# tick-mk-3.net
KiCad netlist of a schematic drawn in EAGLE
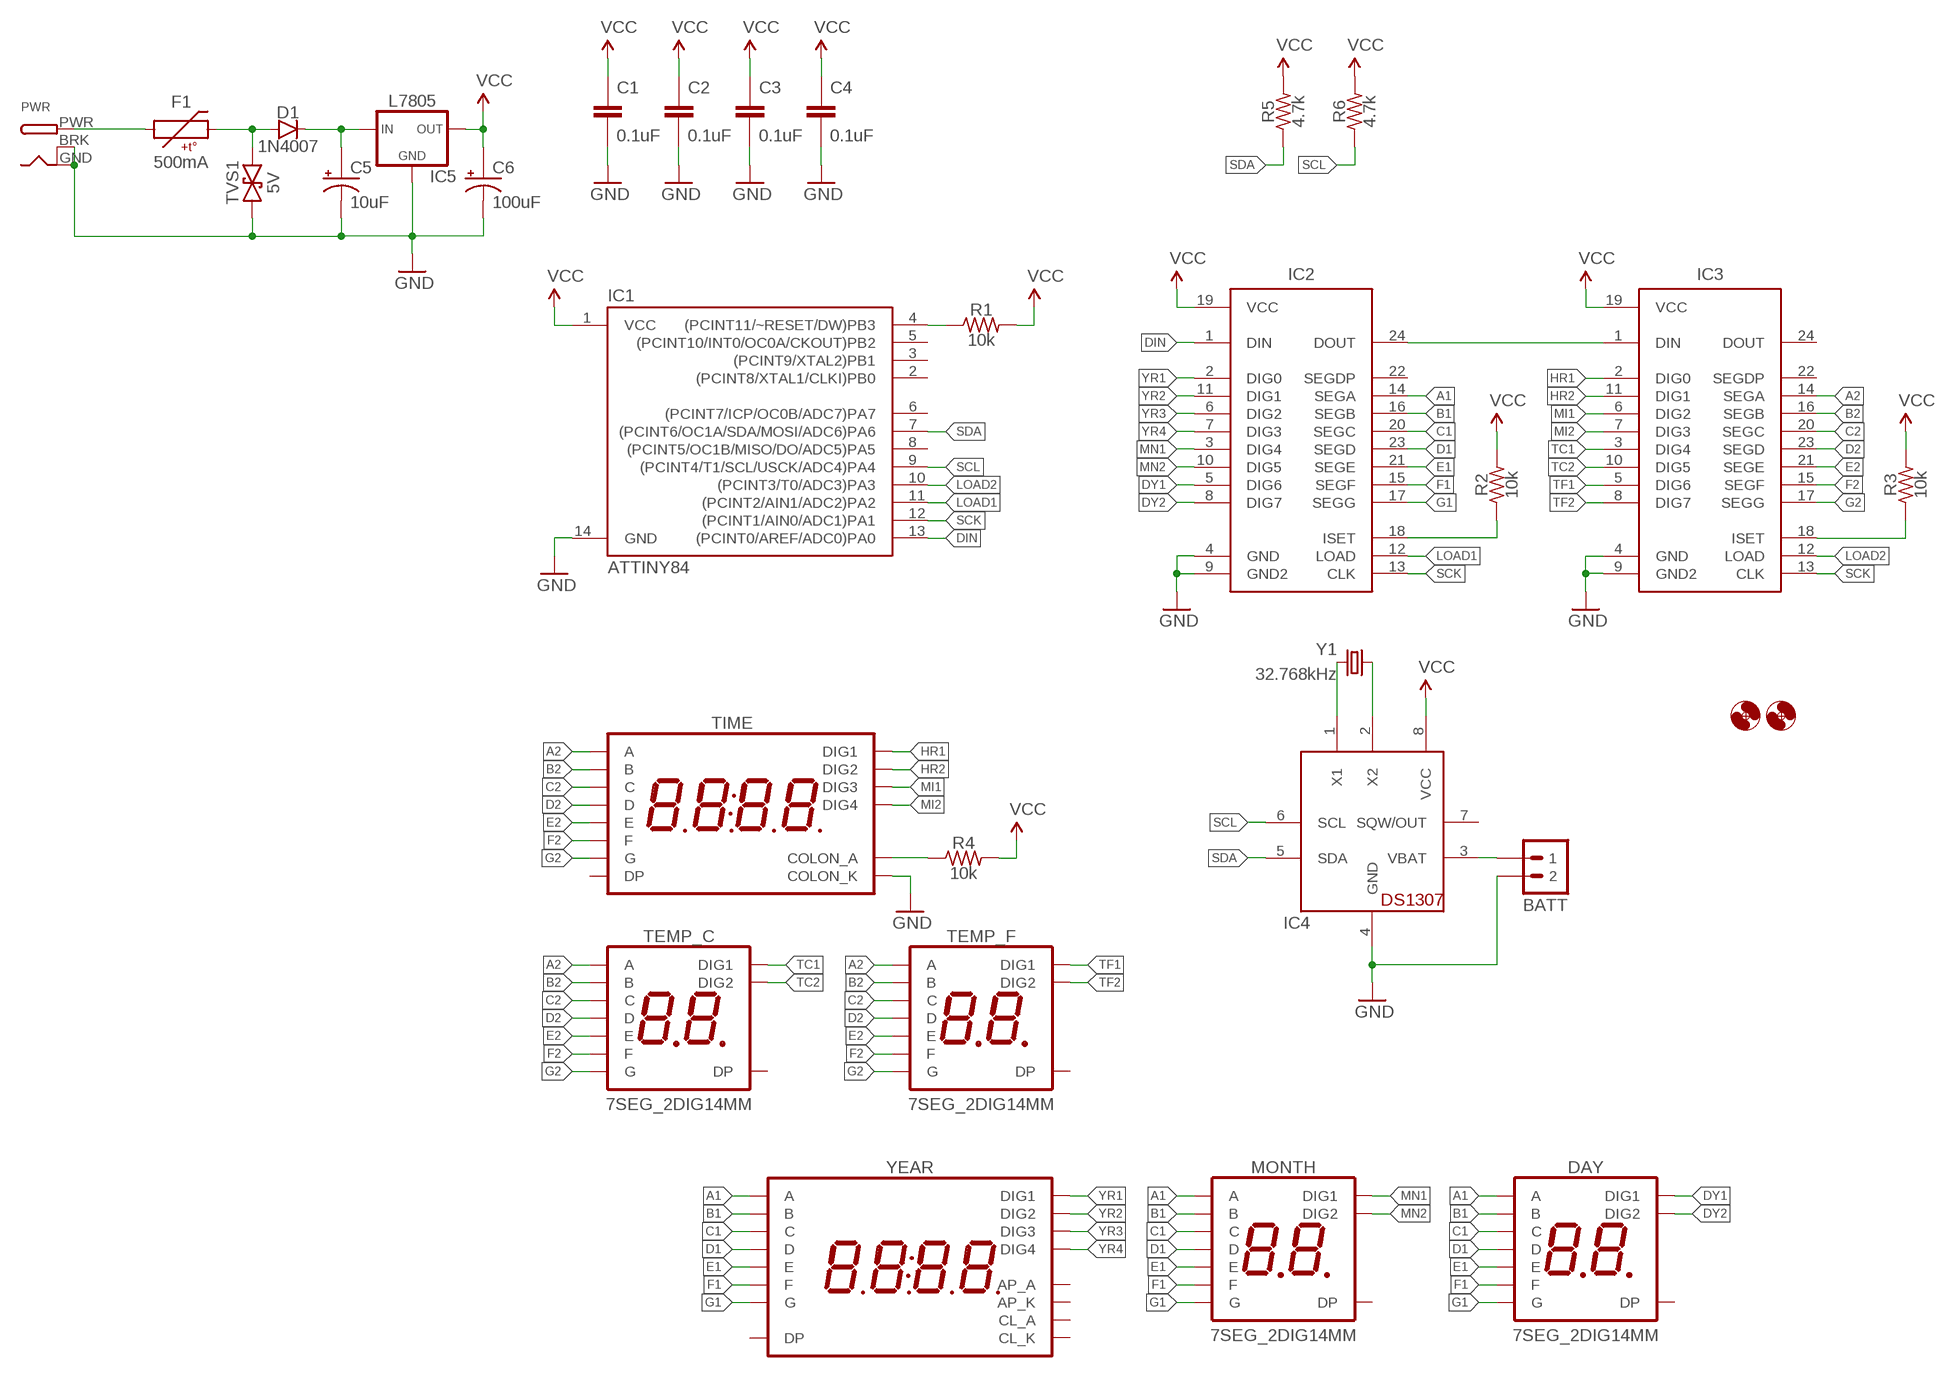
[diagram p0: schematic, sheet 1]

(export (version "E")
  (design (tool "Eeschema 10.0.6"))
  (components
    (comp (ref "BATT")
      (value "M02JST-PTH-VERT")
      (footprint "eagle-import:JST-2-PH-VERT-PTH")
      (libsource (lib "eagle-import") (part "M02JST-PTH-VERT"))
    )
    (comp (ref "C1")
      (value "0.1uF")
      (footprint "eagle-import:C025-024X044")
      (libsource (lib "eagle-import") (part "CAPACITOR-CERAMIC025-024X044"))
    )
    (comp (ref "C2")
      (value "0.1uF")
      (footprint "eagle-import:C025-024X044")
      (libsource (lib "eagle-import") (part "CAPACITOR-CERAMIC025-024X044"))
    )
    (comp (ref "C3")
      (value "0.1uF")
      (footprint "eagle-import:C025-024X044")
      (libsource (lib "eagle-import") (part "CAPACITOR-CERAMIC025-024X044"))
    )
    (comp (ref "C4")
      (value "0.1uF")
      (footprint "eagle-import:C025-024X044")
      (libsource (lib "eagle-import") (part "CAPACITOR-CERAMIC025-024X044"))
    )
    (comp (ref "C5")
      (value "10uF")
      (footprint "eagle-import:E2-5")
      (libsource (lib "eagle-import") (part "CAPACITOR-POLARIZEDE2-5"))
    )
    (comp (ref "C6")
      (value "100uF")
      (footprint "eagle-import:E2-5")
      (libsource (lib "eagle-import") (part "CAPACITOR-POLARIZEDE2-5"))
    )
    (comp (ref "D1")
      (value "1N4007")
      (footprint "eagle-import:DIODE-10.16MM")
      (libsource (lib "eagle-import") (part "DIODEPTH-10.68MM"))
    )
    (comp (ref "DAY")
      (value "7SEG_2DIG14MM")
      (footprint "eagle-import:7SEG_2DIG_14MM")
      (libsource (lib "eagle-import") (part "7SEG_2DIG14MM"))
    )
    (comp (ref "F1")
      (value "500mA")
      (footprint "eagle-import:PTC-PTH-5.08MM")
      (libsource (lib "eagle-import") (part "PTCPTH-5.08MM"))
    )
    (comp (ref "H1")
      (value "HOLE#2")
      (footprint "eagle-import:HOLE-#2")
      (libsource (lib "eagle-import") (part "HOLE#2"))
    )
    (comp (ref "H2")
      (value "HOLE#2")
      (footprint "eagle-import:HOLE-#2")
      (libsource (lib "eagle-import") (part "HOLE#2"))
    )
    (comp (ref "IC1")
      (value "ATTINY84")
      (footprint "eagle-import:SO14")
      (libsource (lib "eagle-import") (part "ATTINY84"))
    )
    (comp (ref "IC2")
      (value "MAX7219")
      (footprint "eagle-import:SO24W")
      (libsource (lib "eagle-import") (part "MAX7219SOIC-W"))
    )
    (comp (ref "IC3")
      (value "MAX7219")
      (footprint "eagle-import:SO24W")
      (libsource (lib "eagle-import") (part "MAX7219SOIC-W"))
    )
    (comp (ref "IC4")
      (value "DS1307")
      (footprint "eagle-import:DIL08")
      (libsource (lib "eagle-import") (part "DS1307"))
    )
    (comp (ref "IC5")
      (value "L7805")
      (footprint "eagle-import:78XXL")
      (libsource (lib "eagle-import") (part "V_REG_78XXSIDE"))
    )
    (comp (ref "MONTH")
      (value "7SEG_2DIG14MM")
      (footprint "eagle-import:7SEG_2DIG_14MM")
      (libsource (lib "eagle-import") (part "7SEG_2DIG14MM"))
    )
    (comp (ref "PWR")
      (value "DCBARRELPTH")
      (footprint "eagle-import:DCJACK_2MM_PTH")
      (libsource (lib "eagle-import") (part "DCBARRELPTH"))
    )
    (comp (ref "R1")
      (value "10k")
      (footprint "eagle-import:RESISTOR-AXIAL-PTH-5.08MM")
      (libsource (lib "eagle-import") (part "RESISTORPTH-AXIAL-5.08MM"))
    )
    (comp (ref "R2")
      (value "10k")
      (footprint "eagle-import:RESISTOR-AXIAL-PTH-5.08MM")
      (libsource (lib "eagle-import") (part "RESISTORPTH-AXIAL-5.08MM"))
    )
    (comp (ref "R3")
      (value "10k")
      (footprint "eagle-import:RESISTOR-AXIAL-PTH-5.08MM")
      (libsource (lib "eagle-import") (part "RESISTORPTH-AXIAL-5.08MM"))
    )
    (comp (ref "R4")
      (value "10k")
      (footprint "eagle-import:RESISTOR-AXIAL-PTH-5.08MM")
      (libsource (lib "eagle-import") (part "RESISTORPTH-AXIAL-5.08MM"))
    )
    (comp (ref "R5")
      (value "4.7k")
      (footprint "eagle-import:RESISTOR-AXIAL-PTH-5.08MM")
      (libsource (lib "eagle-import") (part "RESISTORPTH-AXIAL-5.08MM"))
    )
    (comp (ref "R6")
      (value "4.7k")
      (footprint "eagle-import:RESISTOR-AXIAL-PTH-5.08MM")
      (libsource (lib "eagle-import") (part "RESISTORPTH-AXIAL-5.08MM"))
    )
    (comp (ref "TEMP_C")
      (value "7SEG_2DIG14MM")
      (footprint "eagle-import:7SEG_2DIG_14MM")
      (libsource (lib "eagle-import") (part "7SEG_2DIG14MM"))
    )
    (comp (ref "TEMP_F")
      (value "7SEG_2DIG14MM")
      (footprint "eagle-import:7SEG_2DIG_14MM")
      (libsource (lib "eagle-import") (part "7SEG_2DIG14MM"))
    )
    (comp (ref "TIME")
      (value "7SED_4DIGIT_14MM14.2MM-CC")
      (footprint "eagle-import:7SEG_4DIG")
      (libsource (lib "eagle-import") (part "7SED_4DIGIT_14MM14.2MM-CC"))
    )
    (comp (ref "TVS1")
      (value "5V")
      (footprint "eagle-import:DO-41-TVS")
      (libsource (lib "eagle-import") (part "TVSDO-41-TVS-BIDIRECTIONAL"))
    )
    (comp (ref "Y1")
      (value "32.768kHz")
      (footprint "eagle-import:TC26H")
      (libsource (lib "eagle-import") (part "CRYSTALTC26H"))
    )
    (comp (ref "YEAR")
      (value "7SEG_4DIGIT_10MM")
      (footprint "eagle-import:7SEG_4DIG_10MM")
      (libsource (lib "eagle-import") (part "7SEG_4DIGIT_10MM"))
    )
  )
  (nets
    (net (code "1") (name "A1") (class "Default")
      (node (ref "DAY") (pin "4") (pinfunction "A_4") (pintype "passive"))
      (node (ref "IC2") (pin "14") (pinfunction "SEGA_14") (pintype "bidirectional"))
      (node (ref "MONTH") (pin "4") (pinfunction "A_4") (pintype "passive"))
      (node (ref "YEAR") (pin "14") (pinfunction "A_14") (pintype "passive"))
    )
    (net (code "2") (name "A2") (class "Default")
      (node (ref "IC3") (pin "14") (pinfunction "SEGA_14") (pintype "bidirectional"))
      (node (ref "TEMP_C") (pin "4") (pinfunction "A_4") (pintype "passive"))
      (node (ref "TEMP_F") (pin "4") (pinfunction "A_4") (pintype "passive"))
      (node (ref "TIME") (pin "P$13") (pinfunction "A_P$13") (pintype "passive"))
    )
    (net (code "3") (name "B1") (class "Default")
      (node (ref "DAY") (pin "3") (pinfunction "B_3") (pintype "passive"))
      (node (ref "IC2") (pin "16") (pinfunction "SEGB_16") (pintype "bidirectional"))
      (node (ref "MONTH") (pin "3") (pinfunction "B_3") (pintype "passive"))
      (node (ref "YEAR") (pin "16") (pinfunction "B_16") (pintype "passive"))
    )
    (net (code "4") (name "B2") (class "Default")
      (node (ref "IC3") (pin "16") (pinfunction "SEGB_16") (pintype "bidirectional"))
      (node (ref "TEMP_C") (pin "3") (pinfunction "B_3") (pintype "passive"))
      (node (ref "TEMP_F") (pin "3") (pinfunction "B_3") (pintype "passive"))
      (node (ref "TIME") (pin "P$9") (pinfunction "B_P$9") (pintype "passive"))
    )
    (net (code "5") (name "C1") (class "Default")
      (node (ref "DAY") (pin "9") (pinfunction "C_9") (pintype "passive"))
      (node (ref "IC2") (pin "20") (pinfunction "SEGC_20") (pintype "bidirectional"))
      (node (ref "MONTH") (pin "9") (pinfunction "C_9") (pintype "passive"))
      (node (ref "YEAR") (pin "13") (pinfunction "C_13") (pintype "passive"))
    )
    (net (code "6") (name "C2") (class "Default")
      (node (ref "IC3") (pin "20") (pinfunction "SEGC_20") (pintype "bidirectional"))
      (node (ref "TEMP_C") (pin "9") (pinfunction "C_9") (pintype "passive"))
      (node (ref "TEMP_F") (pin "9") (pinfunction "C_9") (pintype "passive"))
      (node (ref "TIME") (pin "P$4") (pinfunction "C_P$4") (pintype "passive"))
    )
    (net (code "7") (name "D1") (class "Default")
      (node (ref "DAY") (pin "8") (pinfunction "D_8") (pintype "passive"))
      (node (ref "IC2") (pin "23") (pinfunction "SEGD_23") (pintype "bidirectional"))
      (node (ref "MONTH") (pin "8") (pinfunction "D_8") (pintype "passive"))
      (node (ref "YEAR") (pin "3") (pinfunction "D_3") (pintype "passive"))
    )
    (net (code "8") (name "D2") (class "Default")
      (node (ref "IC3") (pin "23") (pinfunction "SEGD_23") (pintype "bidirectional"))
      (node (ref "TEMP_C") (pin "8") (pinfunction "D_8") (pintype "passive"))
      (node (ref "TEMP_F") (pin "8") (pinfunction "D_8") (pintype "passive"))
      (node (ref "TIME") (pin "P$2") (pinfunction "D_P$2") (pintype "passive"))
    )
    (net (code "9") (name "DIN") (class "Default")
      (node (ref "IC1") (pin "13") (pinfunction "(PCINT0/AREF/ADC0)PA0_13") (pintype "bidirectional"))
      (node (ref "IC2") (pin "1") (pinfunction "DIN_1") (pintype "bidirectional"))
    )
    (net (code "10") (name "DY1") (class "Default")
      (node (ref "DAY") (pin "5") (pinfunction "DIG1_5") (pintype "passive"))
      (node (ref "IC2") (pin "5") (pinfunction "DIG6_5") (pintype "bidirectional"))
    )
    (net (code "11") (name "DY2") (class "Default")
      (node (ref "DAY") (pin "10") (pinfunction "DIG2_10") (pintype "passive"))
      (node (ref "IC2") (pin "8") (pinfunction "DIG7_8") (pintype "bidirectional"))
    )
    (net (code "12") (name "E1") (class "Default")
      (node (ref "DAY") (pin "6") (pinfunction "E_6") (pintype "passive"))
      (node (ref "IC2") (pin "21") (pinfunction "SEGE_21") (pintype "bidirectional"))
      (node (ref "MONTH") (pin "6") (pinfunction "E_6") (pintype "passive"))
      (node (ref "YEAR") (pin "5") (pinfunction "E_5") (pintype "passive"))
    )
    (net (code "13") (name "E2") (class "Default")
      (node (ref "IC3") (pin "21") (pinfunction "SEGE_21") (pintype "bidirectional"))
      (node (ref "TEMP_C") (pin "6") (pinfunction "E_6") (pintype "passive"))
      (node (ref "TEMP_F") (pin "6") (pinfunction "E_6") (pintype "passive"))
      (node (ref "TIME") (pin "P$1") (pinfunction "E_P$1") (pintype "passive"))
    )
    (net (code "14") (name "F1") (class "Default")
      (node (ref "DAY") (pin "7") (pinfunction "F_7") (pintype "passive"))
      (node (ref "IC2") (pin "15") (pinfunction "SEGF_15") (pintype "bidirectional"))
      (node (ref "MONTH") (pin "7") (pinfunction "F_7") (pintype "passive"))
      (node (ref "YEAR") (pin "11") (pinfunction "F_11") (pintype "passive"))
    )
    (net (code "15") (name "F2") (class "Default")
      (node (ref "IC3") (pin "15") (pinfunction "SEGF_15") (pintype "bidirectional"))
      (node (ref "TEMP_C") (pin "7") (pinfunction "F_7") (pintype "passive"))
      (node (ref "TEMP_F") (pin "7") (pinfunction "F_7") (pintype "passive"))
      (node (ref "TIME") (pin "P$12") (pinfunction "F_P$12") (pintype "passive"))
    )
    (net (code "16") (name "G1") (class "Default")
      (node (ref "DAY") (pin "1") (pinfunction "G_1") (pintype "passive"))
      (node (ref "IC2") (pin "17") (pinfunction "SEGG_17") (pintype "bidirectional"))
      (node (ref "MONTH") (pin "1") (pinfunction "G_1") (pintype "passive"))
      (node (ref "YEAR") (pin "15") (pinfunction "G_15") (pintype "passive"))
    )
    (net (code "17") (name "G2") (class "Default")
      (node (ref "IC3") (pin "17") (pinfunction "SEGG_17") (pintype "bidirectional"))
      (node (ref "TEMP_C") (pin "1") (pinfunction "G_1") (pintype "passive"))
      (node (ref "TEMP_F") (pin "1") (pinfunction "G_1") (pintype "passive"))
      (node (ref "TIME") (pin "P$5") (pinfunction "G_P$5") (pintype "passive"))
    )
    (net (code "18") (name "GND") (class "Default")
      (node (ref "BATT") (pin "2") (pinfunction "2_2") (pintype "passive"))
      (node (ref "C1") (pin "2") (pinfunction "2_2") (pintype "passive"))
      (node (ref "C2") (pin "2") (pinfunction "2_2") (pintype "passive"))
      (node (ref "C3") (pin "2") (pinfunction "2_2") (pintype "passive"))
      (node (ref "C4") (pin "2") (pinfunction "2_2") (pintype "passive"))
      (node (ref "C5") (pin "-") (pinfunction "-_-") (pintype "passive"))
      (node (ref "C6") (pin "-") (pinfunction "-_-") (pintype "passive"))
      (node (ref "IC1") (pin "14") (pinfunction "GND_14") (pintype "bidirectional"))
      (node (ref "IC2") (pin "4") (pinfunction "GND_4") (pintype "bidirectional"))
      (node (ref "IC2") (pin "9") (pinfunction "GND2_9") (pintype "bidirectional"))
      (node (ref "IC3") (pin "4") (pinfunction "GND_4") (pintype "bidirectional"))
      (node (ref "IC3") (pin "9") (pinfunction "GND2_9") (pintype "bidirectional"))
      (node (ref "IC4") (pin "4") (pinfunction "GND_4") (pintype "power_in"))
      (node (ref "IC5") (pin "GND") (pinfunction "GND_GND") (pintype "input"))
      (node (ref "PWR") (pin "BRK") (pinfunction "BRK_BRK") (pintype "power_in"))
      (node (ref "PWR") (pin "GND") (pinfunction "GND_GND") (pintype "power_in"))
      (node (ref "TIME") (pin "P$7") (pinfunction "COLON_K_P$7") (pintype "passive"))
      (node (ref "TVS1") (pin "P$1") (pinfunction "1_P$1") (pintype "passive"))
    )
    (net (code "19") (name "HR1") (class "Default")
      (node (ref "IC3") (pin "2") (pinfunction "DIG0_2") (pintype "bidirectional"))
      (node (ref "TIME") (pin "P$14") (pinfunction "DIG1_P$14") (pintype "passive"))
    )
    (net (code "20") (name "HR2") (class "Default")
      (node (ref "IC3") (pin "11") (pinfunction "DIG1_11") (pintype "bidirectional"))
      (node (ref "TIME") (pin "P$11") (pinfunction "DIG2_P$11") (pintype "passive"))
    )
    (net (code "21") (name "LOAD1") (class "Default")
      (node (ref "IC1") (pin "11") (pinfunction "(PCINT2/AIN1/ADC2)PA2_11") (pintype "bidirectional"))
      (node (ref "IC2") (pin "12") (pinfunction "LOAD_12") (pintype "bidirectional"))
    )
    (net (code "22") (name "LOAD2") (class "Default")
      (node (ref "IC1") (pin "10") (pinfunction "(PCINT3/T0/ADC3)PA3_10") (pintype "bidirectional"))
      (node (ref "IC3") (pin "12") (pinfunction "LOAD_12") (pintype "bidirectional"))
    )
    (net (code "23") (name "MI1") (class "Default")
      (node (ref "IC3") (pin "6") (pinfunction "DIG2_6") (pintype "bidirectional"))
      (node (ref "TIME") (pin "P$10") (pinfunction "DIG3_P$10") (pintype "passive"))
    )
    (net (code "24") (name "MI2") (class "Default")
      (node (ref "IC3") (pin "7") (pinfunction "DIG3_7") (pintype "bidirectional"))
      (node (ref "TIME") (pin "P$6") (pinfunction "DIG4_P$6") (pintype "passive"))
    )
    (net (code "25") (name "MN1") (class "Default")
      (node (ref "IC2") (pin "3") (pinfunction "DIG4_3") (pintype "bidirectional"))
      (node (ref "MONTH") (pin "5") (pinfunction "DIG1_5") (pintype "passive"))
    )
    (net (code "26") (name "MN2") (class "Default")
      (node (ref "IC2") (pin "10") (pinfunction "DIG5_10") (pintype "bidirectional"))
      (node (ref "MONTH") (pin "10") (pinfunction "DIG2_10") (pintype "passive"))
    )
    (net (code "27") (name "Net-(C5-Pad+)") (class "Default")
      (node (ref "C5") (pin "+") (pinfunction "+_+") (pintype "passive"))
      (node (ref "D1") (pin "C") (pinfunction "C_C") (pintype "passive"))
      (node (ref "IC5") (pin "IN") (pinfunction "IN_IN") (pintype "input"))
    )
    (net (code "28") (name "Net-(F1-1)") (class "Default")
      (node (ref "F1") (pin "P$1") (pinfunction "1_P$1") (pintype "passive"))
      (node (ref "PWR") (pin "PWR") (pinfunction "PWR_PWR") (pintype "power_in"))
    )
    (net (code "29") (name "Net-(F1-2)") (class "Default")
      (node (ref "D1") (pin "A") (pinfunction "A_A") (pintype "passive"))
      (node (ref "F1") (pin "P$2") (pinfunction "2_P$2") (pintype "passive"))
      (node (ref "TVS1") (pin "P$2") (pinfunction "2_P$2") (pintype "passive"))
    )
    (net (code "30") (name "Net-(IC1-(PCINT11{slash}~{RESET{slash}DW})PB3)") (class "Default")
      (node (ref "IC1") (pin "4") (pinfunction "(PCINT11/~{RESET/DW})PB3_4") (pintype "bidirectional"))
      (node (ref "R1") (pin "P$1") (pinfunction "1_P$1") (pintype "passive"))
    )
    (net (code "31") (name "Net-(IC2-DOUT)") (class "Default")
      (node (ref "IC2") (pin "24") (pinfunction "DOUT_24") (pintype "bidirectional"))
      (node (ref "IC3") (pin "1") (pinfunction "DIN_1") (pintype "bidirectional"))
    )
    (net (code "32") (name "Net-(IC2-ISET)") (class "Default")
      (node (ref "IC2") (pin "18") (pinfunction "ISET_18") (pintype "bidirectional"))
      (node (ref "R2") (pin "P$1") (pinfunction "1_P$1") (pintype "passive"))
    )
    (net (code "33") (name "Net-(IC3-ISET)") (class "Default")
      (node (ref "IC3") (pin "18") (pinfunction "ISET_18") (pintype "bidirectional"))
      (node (ref "R3") (pin "P$1") (pinfunction "1_P$1") (pintype "passive"))
    )
    (net (code "34") (name "Net-(IC4-VBAT)") (class "Default")
      (node (ref "BATT") (pin "1") (pinfunction "1_1") (pintype "passive"))
      (node (ref "IC4") (pin "3") (pinfunction "VBAT_3") (pintype "power_in"))
    )
    (net (code "35") (name "Net-(IC4-X1)") (class "Default")
      (node (ref "IC4") (pin "1") (pinfunction "X1_1") (pintype "passive"))
      (node (ref "Y1") (pin "2") (pinfunction "2_2") (pintype "passive"))
    )
    (net (code "36") (name "Net-(IC4-X2)") (class "Default")
      (node (ref "IC4") (pin "2") (pinfunction "X2_2") (pintype "passive"))
      (node (ref "Y1") (pin "1") (pinfunction "1_1") (pintype "passive"))
    )
    (net (code "37") (name "Net-(R4-1)") (class "Default")
      (node (ref "R4") (pin "P$1") (pinfunction "1_P$1") (pintype "passive"))
      (node (ref "TIME") (pin "P$8") (pinfunction "COLON_A_P$8") (pintype "passive"))
    )
    (net (code "38") (name "SCK") (class "Default")
      (node (ref "IC1") (pin "12") (pinfunction "(PCINT1/AIN0/ADC1)PA1_12") (pintype "bidirectional"))
      (node (ref "IC2") (pin "13") (pinfunction "CLK_13") (pintype "bidirectional"))
      (node (ref "IC3") (pin "13") (pinfunction "CLK_13") (pintype "bidirectional"))
    )
    (net (code "39") (name "SCL") (class "Default")
      (node (ref "IC1") (pin "9") (pinfunction "(PCINT4/T1/SCL/USCK/ADC4)PA4_9") (pintype "bidirectional"))
      (node (ref "IC4") (pin "6") (pinfunction "SCL_6") (pintype "bidirectional"))
      (node (ref "R6") (pin "P$1") (pinfunction "1_P$1") (pintype "passive"))
    )
    (net (code "40") (name "SDA") (class "Default")
      (node (ref "IC1") (pin "7") (pinfunction "(PCINT6/OC1A/SDA/MOSI/ADC6)PA6_7") (pintype "bidirectional"))
      (node (ref "IC4") (pin "5") (pinfunction "SDA_5") (pintype "bidirectional"))
      (node (ref "R5") (pin "P$1") (pinfunction "1_P$1") (pintype "passive"))
    )
    (net (code "41") (name "TC1") (class "Default")
      (node (ref "IC3") (pin "3") (pinfunction "DIG4_3") (pintype "bidirectional"))
      (node (ref "TEMP_C") (pin "5") (pinfunction "DIG1_5") (pintype "passive"))
    )
    (net (code "42") (name "TC2") (class "Default")
      (node (ref "IC3") (pin "10") (pinfunction "DIG5_10") (pintype "bidirectional"))
      (node (ref "TEMP_C") (pin "10") (pinfunction "DIG2_10") (pintype "passive"))
    )
    (net (code "43") (name "TF1") (class "Default")
      (node (ref "IC3") (pin "5") (pinfunction "DIG6_5") (pintype "bidirectional"))
      (node (ref "TEMP_F") (pin "5") (pinfunction "DIG1_5") (pintype "passive"))
    )
    (net (code "44") (name "TF2") (class "Default")
      (node (ref "IC3") (pin "8") (pinfunction "DIG7_8") (pintype "bidirectional"))
      (node (ref "TEMP_F") (pin "10") (pinfunction "DIG2_10") (pintype "passive"))
    )
    (net (code "45") (name "VCC") (class "Default")
      (node (ref "C1") (pin "1") (pinfunction "1_1") (pintype "passive"))
      (node (ref "C2") (pin "1") (pinfunction "1_1") (pintype "passive"))
      (node (ref "C3") (pin "1") (pinfunction "1_1") (pintype "passive"))
      (node (ref "C4") (pin "1") (pinfunction "1_1") (pintype "passive"))
      (node (ref "C6") (pin "+") (pinfunction "+_+") (pintype "passive"))
      (node (ref "IC1") (pin "1") (pinfunction "VCC_1") (pintype "bidirectional"))
      (node (ref "IC2") (pin "19") (pinfunction "VCC_19") (pintype "bidirectional"))
      (node (ref "IC3") (pin "19") (pinfunction "VCC_19") (pintype "bidirectional"))
      (node (ref "IC4") (pin "8") (pinfunction "VCC_8") (pintype "power_in"))
      (node (ref "IC5") (pin "OUT") (pinfunction "OUT_OUT") (pintype "output"))
      (node (ref "R1") (pin "P$2") (pinfunction "2_P$2") (pintype "passive"))
      (node (ref "R2") (pin "P$2") (pinfunction "2_P$2") (pintype "passive"))
      (node (ref "R3") (pin "P$2") (pinfunction "2_P$2") (pintype "passive"))
      (node (ref "R4") (pin "P$2") (pinfunction "2_P$2") (pintype "passive"))
      (node (ref "R5") (pin "P$2") (pinfunction "2_P$2") (pintype "passive"))
      (node (ref "R6") (pin "P$2") (pinfunction "2_P$2") (pintype "passive"))
    )
    (net (code "46") (name "YR1") (class "Default")
      (node (ref "IC2") (pin "2") (pinfunction "DIG0_2") (pintype "bidirectional"))
      (node (ref "YEAR") (pin "1") (pinfunction "DIG1_1") (pintype "passive"))
    )
    (net (code "47") (name "YR2") (class "Default")
      (node (ref "IC2") (pin "11") (pinfunction "DIG1_11") (pintype "bidirectional"))
      (node (ref "YEAR") (pin "2") (pinfunction "DIG2_2") (pintype "passive"))
    )
    (net (code "48") (name "YR3") (class "Default")
      (node (ref "IC2") (pin "6") (pinfunction "DIG2_6") (pintype "bidirectional"))
      (node (ref "YEAR") (pin "6") (pinfunction "DIG3_6") (pintype "passive"))
    )
    (net (code "49") (name "YR4") (class "Default")
      (node (ref "IC2") (pin "7") (pinfunction "DIG3_7") (pintype "bidirectional"))
      (node (ref "YEAR") (pin "8") (pinfunction "DIG4_8") (pintype "passive"))
    )
    (net (code "50") (name "unconnected-(DAY-DP-Pad2)") (class "Default")
      (node (ref "DAY") (pin "2") (pinfunction "DP_2") (pintype "passive"))
    )
    (net (code "51") (name "unconnected-(IC1-(PCINT5{slash}OC1B{slash}MISO{slash}DO{slash}ADC5)PA5-Pad8)") (class "Default")
      (node (ref "IC1") (pin "8") (pinfunction "(PCINT5/OC1B/MISO/DO/ADC5)PA5_8") (pintype "bidirectional"))
    )
    (net (code "52") (name "unconnected-(IC1-(PCINT7{slash}ICP{slash}OC0B{slash}ADC7)PA7-Pad6)") (class "Default")
      (node (ref "IC1") (pin "6") (pinfunction "(PCINT7/ICP/OC0B/ADC7)PA7_6") (pintype "bidirectional"))
    )
    (net (code "53") (name "unconnected-(IC1-(PCINT8{slash}XTAL1{slash}CLKI)PB0-Pad2)") (class "Default")
      (node (ref "IC1") (pin "2") (pinfunction "(PCINT8/XTAL1/CLKI)PB0_2") (pintype "bidirectional"))
    )
    (net (code "54") (name "unconnected-(IC1-(PCINT9{slash}XTAL2)PB1-Pad3)") (class "Default")
      (node (ref "IC1") (pin "3") (pinfunction "(PCINT9/XTAL2)PB1_3") (pintype "bidirectional"))
    )
    (net (code "55") (name "unconnected-(IC1-(PCINT10{slash}INT0{slash}OC0A{slash}CKOUT)PB2-Pad5)") (class "Default")
      (node (ref "IC1") (pin "5") (pinfunction "(PCINT10/INT0/OC0A/CKOUT)PB2_5") (pintype "bidirectional"))
    )
    (net (code "56") (name "unconnected-(IC2-SEGDP-Pad22)") (class "Default")
      (node (ref "IC2") (pin "22") (pinfunction "SEGDP_22") (pintype "bidirectional"))
    )
    (net (code "57") (name "unconnected-(IC3-DOUT-Pad24)") (class "Default")
      (node (ref "IC3") (pin "24") (pinfunction "DOUT_24") (pintype "bidirectional"))
    )
    (net (code "58") (name "unconnected-(IC3-SEGDP-Pad22)") (class "Default")
      (node (ref "IC3") (pin "22") (pinfunction "SEGDP_22") (pintype "bidirectional"))
    )
    (net (code "59") (name "unconnected-(IC4-SQW{slash}OUT-Pad7)") (class "Default")
      (node (ref "IC4") (pin "7") (pinfunction "SQW/OUT_7") (pintype "bidirectional"))
    )
    (net (code "60") (name "unconnected-(MONTH-DP-Pad2)") (class "Default")
      (node (ref "MONTH") (pin "2") (pinfunction "DP_2") (pintype "passive"))
    )
    (net (code "61") (name "unconnected-(TEMP_C-DP-Pad2)") (class "Default")
      (node (ref "TEMP_C") (pin "2") (pinfunction "DP_2") (pintype "passive"))
    )
    (net (code "62") (name "unconnected-(TEMP_F-DP-Pad2)") (class "Default")
      (node (ref "TEMP_F") (pin "2") (pinfunction "DP_2") (pintype "passive"))
    )
    (net (code "63") (name "unconnected-(TIME-DP-PadP$3)") (class "Default")
      (node (ref "TIME") (pin "P$3") (pinfunction "DP_P$3") (pintype "passive"))
    )
    (net (code "64") (name "unconnected-(YEAR-AP_A-Pad10)") (class "Default")
      (node (ref "YEAR") (pin "10") (pinfunction "AP_A_10") (pintype "bidirectional"))
    )
    (net (code "65") (name "unconnected-(YEAR-AP_K-Pad9)") (class "Default")
      (node (ref "YEAR") (pin "9") (pinfunction "AP_K_9") (pintype "bidirectional"))
    )
    (net (code "66") (name "unconnected-(YEAR-CL_A-Pad4)") (class "Default")
      (node (ref "YEAR") (pin "4") (pinfunction "CL_A_4") (pintype "passive"))
    )
    (net (code "67") (name "unconnected-(YEAR-CL_K-Pad12)") (class "Default")
      (node (ref "YEAR") (pin "12") (pinfunction "CL_K_12") (pintype "passive"))
    )
    (net (code "68") (name "unconnected-(YEAR-DP-Pad7)") (class "Default")
      (node (ref "YEAR") (pin "7") (pinfunction "DP_7") (pintype "passive"))
    )
  )
)
